# busbar.net
KiCad netlist of a schematic drawn in EAGLE
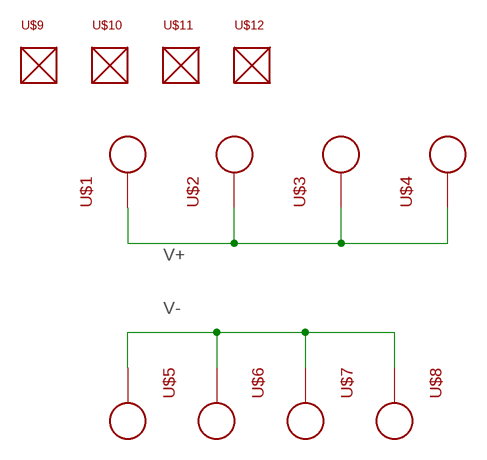
[diagram p0: schematic, sheet 1]

(export (version "E")
  (design (tool "Eeschema 10.0.6"))
  (components
    (comp (ref "U$1")
      (value "PAD12AWG_PAD")
      (footprint "eagle-import:12AWG_PAD")
      (libsource (lib "eagle-import") (part "PAD12AWG_PAD"))
    )
    (comp (ref "U$2")
      (value "PAD12AWG_PAD")
      (footprint "eagle-import:12AWG_PAD")
      (libsource (lib "eagle-import") (part "PAD12AWG_PAD"))
    )
    (comp (ref "U$3")
      (value "PAD12AWG_PAD")
      (footprint "eagle-import:12AWG_PAD")
      (libsource (lib "eagle-import") (part "PAD12AWG_PAD"))
    )
    (comp (ref "U$4")
      (value "PAD12AWG_PAD")
      (footprint "eagle-import:12AWG_PAD")
      (libsource (lib "eagle-import") (part "PAD12AWG_PAD"))
    )
    (comp (ref "U$5")
      (value "PAD12AWG_PAD")
      (footprint "eagle-import:12AWG_PAD")
      (libsource (lib "eagle-import") (part "PAD12AWG_PAD"))
    )
    (comp (ref "U$6")
      (value "PAD12AWG_PAD")
      (footprint "eagle-import:12AWG_PAD")
      (libsource (lib "eagle-import") (part "PAD12AWG_PAD"))
    )
    (comp (ref "U$7")
      (value "PAD12AWG_PAD")
      (footprint "eagle-import:12AWG_PAD")
      (libsource (lib "eagle-import") (part "PAD12AWG_PAD"))
    )
    (comp (ref "U$8")
      (value "PAD12AWG_PAD")
      (footprint "eagle-import:12AWG_PAD")
      (libsource (lib "eagle-import") (part "PAD12AWG_PAD"))
    )
    (comp (ref "U$9")
      (value "MOUNTM2")
      (footprint "eagle-import:M2MOUNT")
      (libsource (lib "eagle-import") (part "MOUNTM2"))
    )
    (comp (ref "U$10")
      (value "MOUNTM2")
      (footprint "eagle-import:M2MOUNT")
      (libsource (lib "eagle-import") (part "MOUNTM2"))
    )
    (comp (ref "U$11")
      (value "MOUNTM2")
      (footprint "eagle-import:M2MOUNT")
      (libsource (lib "eagle-import") (part "MOUNTM2"))
    )
    (comp (ref "U$12")
      (value "MOUNTM2")
      (footprint "eagle-import:M2MOUNT")
      (libsource (lib "eagle-import") (part "MOUNTM2"))
    )
  )
  (nets
    (net (code "1") (name "/V+") (class "Default")
      (node (ref "U$1") (pin "1") (pinfunction "P$1_1") (pintype "bidirectional"))
      (node (ref "U$2") (pin "1") (pinfunction "P$1_1") (pintype "bidirectional"))
      (node (ref "U$3") (pin "1") (pinfunction "P$1_1") (pintype "bidirectional"))
      (node (ref "U$4") (pin "1") (pinfunction "P$1_1") (pintype "bidirectional"))
    )
    (net (code "2") (name "/V-") (class "Default")
      (node (ref "U$5") (pin "1") (pinfunction "P$1_1") (pintype "bidirectional"))
      (node (ref "U$6") (pin "1") (pinfunction "P$1_1") (pintype "bidirectional"))
      (node (ref "U$7") (pin "1") (pinfunction "P$1_1") (pintype "bidirectional"))
      (node (ref "U$8") (pin "1") (pinfunction "P$1_1") (pintype "bidirectional"))
    )
  )
)
